# BasicLEDBadge.net
KiCad netlist of a schematic drawn in EAGLE
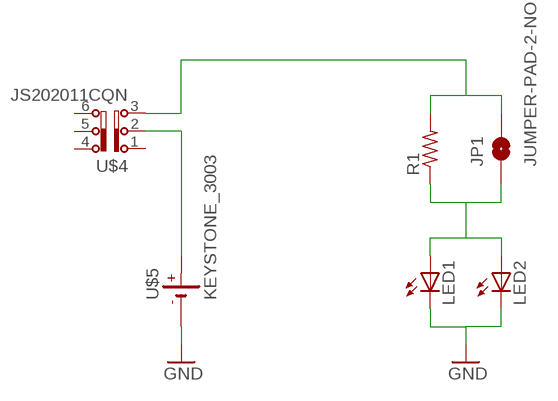
[diagram p0: schematic, sheet 1]

(export (version "E")
  (design (tool "Eeschema 10.0.6"))
  (components
    (comp (ref "JP1")
      (value "JUMPER-PAD-2-NO")
      (footprint "eagle-import:PAD-JUMPER-2-NO_NO_SILK")
      (libsource (lib "eagle-import") (part "JUMPER-PAD-2-NO"))
    )
    (comp (ref "LED1")
      (value "LED5MM")
      (footprint "eagle-import:LED5MM")
      (libsource (lib "eagle-import") (part "LED5MM"))
    )
    (comp (ref "LED2")
      (value "LED5MM")
      (footprint "eagle-import:LED5MM")
      (libsource (lib "eagle-import") (part "LED5MM"))
    )
    (comp (ref "R1")
      (value "R-US_0207/9")
      (footprint "eagle-import:0207_9")
      (libsource (lib "eagle-import") (part "R-US_0207/9"))
    )
    (comp (ref "U$4")
      (value "JS202011CQN")
      (footprint "eagle-import:JS202011CQN")
      (libsource (lib "eagle-import") (part "JS202011CQN"))
    )
    (comp (ref "U$5")
      (value "KEYSTONE_3003")
      (footprint "eagle-import:KEYSTONE_3003")
      (libsource (lib "eagle-import") (part "KEYSTONE_3003"))
    )
  )
  (nets
    (net (code "1") (name "GND") (class "Default")
      (node (ref "LED1") (pin "K") (pinfunction "C_K") (pintype "passive"))
      (node (ref "LED2") (pin "K") (pinfunction "C_K") (pintype "passive"))
      (node (ref "U$5") (pin "P$3") (pinfunction "-_P$3") (pintype "passive"))
    )
    (net (code "2") (name "Net-(JP1-Pad1)") (class "Default")
      (node (ref "JP1") (pin "1") (pinfunction "1_1") (pintype "passive"))
      (node (ref "LED1") (pin "A") (pinfunction "A_A") (pintype "passive"))
      (node (ref "LED2") (pin "A") (pinfunction "A_A") (pintype "passive"))
      (node (ref "R1") (pin "1") (pinfunction "1_1") (pintype "passive"))
    )
    (net (code "3") (name "Net-(JP1-Pad2)") (class "Default")
      (node (ref "JP1") (pin "2") (pinfunction "2_2") (pintype "passive"))
      (node (ref "R1") (pin "2") (pinfunction "2_2") (pintype "passive"))
      (node (ref "U$4") (pin "3") (pinfunction "3_3") (pintype "passive"))
    )
    (net (code "4") (name "Net-(U$4-Pad2)") (class "Default")
      (node (ref "U$4") (pin "2") (pinfunction "2_2") (pintype "passive"))
      (node (ref "U$5") (pin "P$1") (pinfunction "+_P$1") (pintype "passive"))
      (node (ref "U$5") (pin "P$2") (pinfunction "+_P$2") (pintype "passive"))
    )
    (net (code "5") (name "unconnected-(U$4-Pad1)") (class "Default")
      (node (ref "U$4") (pin "1") (pinfunction "1_1") (pintype "passive"))
    )
    (net (code "6") (name "unconnected-(U$4-Pad4)") (class "Default")
      (node (ref "U$4") (pin "4") (pinfunction "4_4") (pintype "passive"))
    )
    (net (code "7") (name "unconnected-(U$4-Pad5)") (class "Default")
      (node (ref "U$4") (pin "5") (pinfunction "5_5") (pintype "passive"))
    )
    (net (code "8") (name "unconnected-(U$4-Pad6)") (class "Default")
      (node (ref "U$4") (pin "6") (pinfunction "6_6") (pintype "passive"))
    )
  )
)
